# LED.net
KiCad netlist of a schematic drawn in Altium Designer
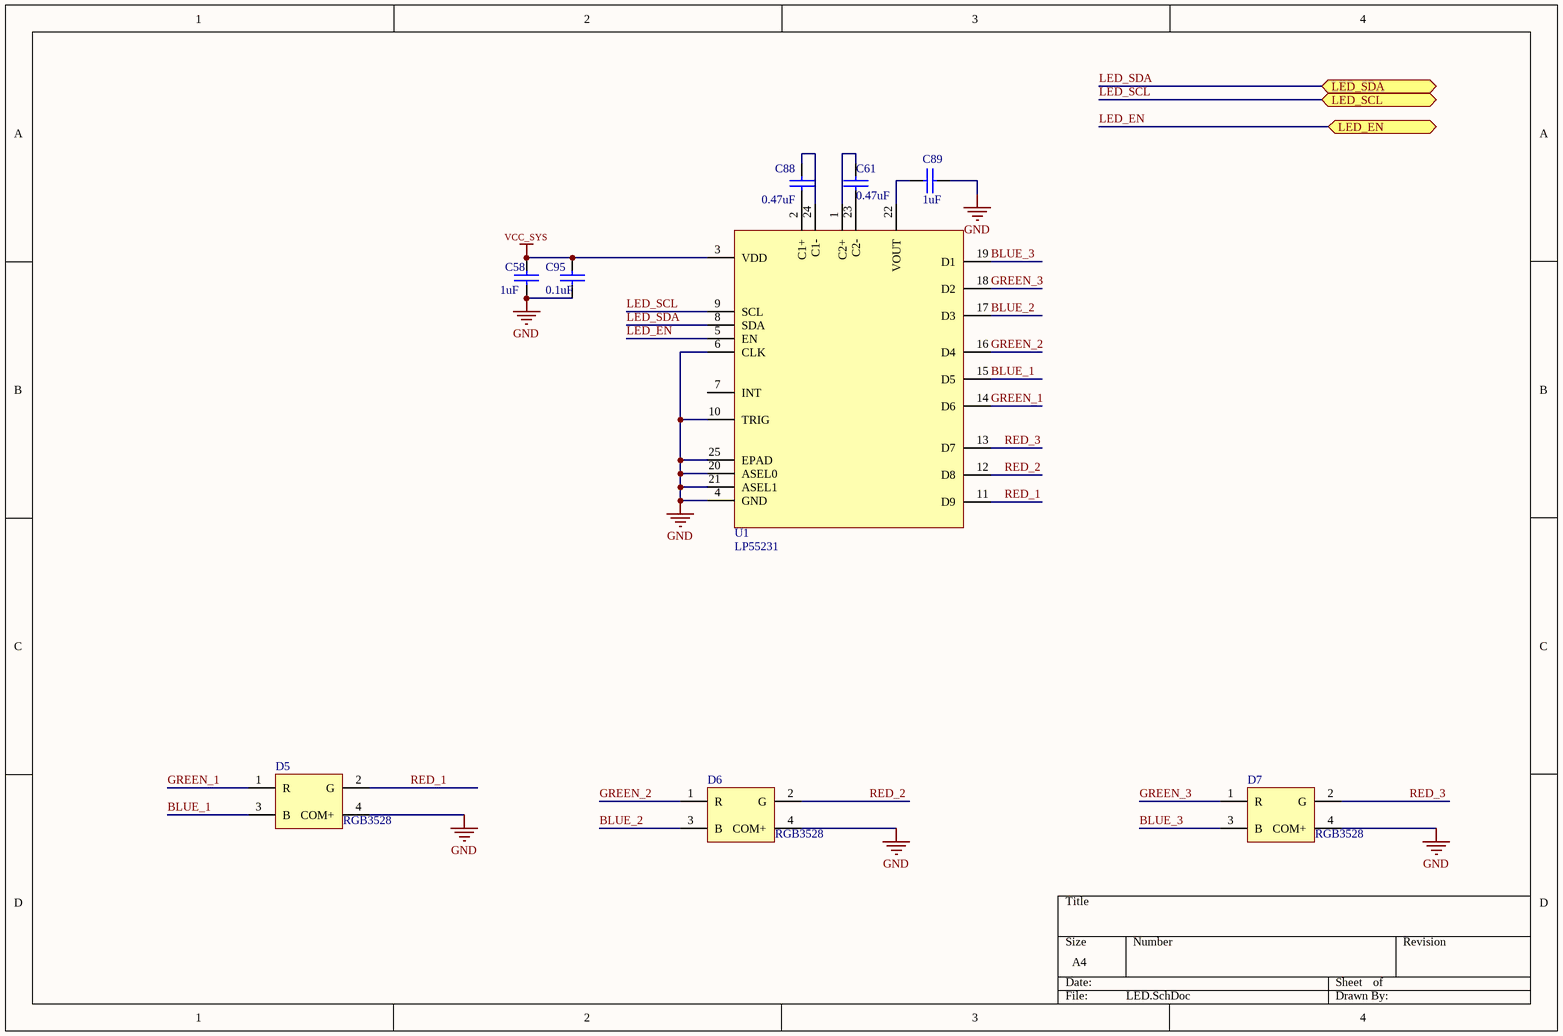
[diagram p0: LED.SchDoc]

(export (version "E")
  (design (tool "Eeschema 10.0.6"))
  (components
    (comp (ref "C58")
      (value "1uF")
      (footprint "0402C")
      (description "1uF/10V/X7R/10%，0402")
      (libsource (lib "Schlib1") (part "CAP"))
    )
    (comp (ref "C61")
      (value "0.47uF")
      (footprint "0402C")
      (description "0.1uF/10V/X7R/10%，0402")
      (libsource (lib "Schlib1") (part "CAP"))
    )
    (comp (ref "C88")
      (value "0.47uF")
      (footprint "0402C")
      (description "0.22uF/10V/X7R/10%，0402")
      (libsource (lib "Schlib1") (part "CAP"))
    )
    (comp (ref "C89")
      (value "1uF")
      (footprint "0402C")
      (description "0.22uF/10V/X7R/10%，0402")
      (libsource (lib "Schlib1") (part "CAP"))
    )
    (comp (ref "C95")
      (value "0.1uF")
      (footprint "0402C")
      (description "0.1uF/10V/X7R/10%，0402")
      (libsource (lib "Schlib1") (part "CAP"))
    )
    (comp (ref "D5")
      (value "RGB3528")
      (footprint "19-237B/R6GHBHC-C01/2T")
      (fields (field (name "PUBLISHER") "Altium Limited"))
      (libsource (lib "常用sch库") (part "RGB3528"))
    )
    (comp (ref "D6")
      (value "RGB3528")
      (footprint "19-237B/R6GHBHC-C01/2T")
      (fields (field (name "PUBLISHER") "Altium Limited"))
      (libsource (lib "常用sch库") (part "RGB3528"))
    )
    (comp (ref "D7")
      (value "RGB3528")
      (footprint "19-237B/R6GHBHC-C01/2T")
      (fields (field (name "PUBLISHER") "Altium Limited"))
      (libsource (lib "常用sch库") (part "RGB3528"))
    )
    (comp (ref "U1")
      (value "LP55231")
      (footprint "WQFN24")
      (description "厂家：SI-EN，型号：IS31FL3199-QFLS2-TR")
      (libsource (lib "button_1") (part "SN3199"))
    )
  )
  (nets
    (net (code "1") (name "/BLUE_1") (class "Default")
      (node (ref "D5") (pin "3") (pinfunction "B_3") (pintype "passive"))
      (node (ref "U1") (pin "15") (pinfunction "D5_15") (pintype "passive"))
    )
    (net (code "2") (name "/BLUE_2") (class "Default")
      (node (ref "D6") (pin "3") (pinfunction "B_3") (pintype "passive"))
      (node (ref "U1") (pin "17") (pinfunction "D3_17") (pintype "passive"))
    )
    (net (code "3") (name "/BLUE_3") (class "Default")
      (node (ref "D7") (pin "3") (pinfunction "B_3") (pintype "passive"))
      (node (ref "U1") (pin "19") (pinfunction "D1_19") (pintype "passive"))
    )
    (net (code "4") (name "/GREEN_1") (class "Default")
      (node (ref "D5") (pin "1") (pinfunction "R_1") (pintype "passive"))
      (node (ref "U1") (pin "14") (pinfunction "D6_14") (pintype "passive"))
    )
    (net (code "5") (name "/GREEN_2") (class "Default")
      (node (ref "D6") (pin "1") (pinfunction "R_1") (pintype "passive"))
      (node (ref "U1") (pin "16") (pinfunction "D4_16") (pintype "passive"))
    )
    (net (code "6") (name "/GREEN_3") (class "Default")
      (node (ref "D7") (pin "1") (pinfunction "R_1") (pintype "passive"))
      (node (ref "U1") (pin "18") (pinfunction "D2_18") (pintype "passive"))
    )
    (net (code "7") (name "/LED_EN") (class "Default")
      (node (ref "U1") (pin "5") (pinfunction "EN_5") (pintype "passive"))
    )
    (net (code "8") (name "/LED_SCL") (class "Default")
      (node (ref "U1") (pin "9") (pinfunction "SCL_9") (pintype "passive"))
    )
    (net (code "9") (name "/LED_SDA") (class "Default")
      (node (ref "U1") (pin "8") (pinfunction "SDA_8") (pintype "passive"))
    )
    (net (code "10") (name "/RED_1") (class "Default")
      (node (ref "D5") (pin "2") (pinfunction "G_2") (pintype "passive"))
      (node (ref "U1") (pin "11") (pinfunction "D9_11") (pintype "passive"))
    )
    (net (code "11") (name "/RED_2") (class "Default")
      (node (ref "D6") (pin "2") (pinfunction "G_2") (pintype "passive"))
      (node (ref "U1") (pin "12") (pinfunction "D8_12") (pintype "passive"))
    )
    (net (code "12") (name "/RED_3") (class "Default")
      (node (ref "D7") (pin "2") (pinfunction "G_2") (pintype "passive"))
      (node (ref "U1") (pin "13") (pinfunction "D7_13") (pintype "passive"))
    )
    (net (code "13") (name "GND") (class "Default")
      (node (ref "C58") (pin "2") (pinfunction "2_2") (pintype "passive"))
      (node (ref "C89") (pin "1") (pinfunction "1_1") (pintype "passive"))
      (node (ref "C95") (pin "2") (pinfunction "2_2") (pintype "passive"))
      (node (ref "D5") (pin "4") (pinfunction "COM+_4") (pintype "passive"))
      (node (ref "D6") (pin "4") (pinfunction "COM+_4") (pintype "passive"))
      (node (ref "D7") (pin "4") (pinfunction "COM+_4") (pintype "passive"))
      (node (ref "U1") (pin "10") (pinfunction "TRIG_10") (pintype "passive"))
      (node (ref "U1") (pin "20") (pinfunction "ASEL0_20") (pintype "passive"))
      (node (ref "U1") (pin "21") (pinfunction "ASEL1_21") (pintype "passive"))
      (node (ref "U1") (pin "25") (pinfunction "EPAD_25") (pintype "passive"))
      (node (ref "U1") (pin "4") (pinfunction "GND_4") (pintype "passive"))
      (node (ref "U1") (pin "6") (pinfunction "CLK_6") (pintype "passive"))
    )
    (net (code "14") (name "Net-(U1-C1+)") (class "Default")
      (node (ref "C88") (pin "1") (pinfunction "1_1") (pintype "passive"))
      (node (ref "U1") (pin "2") (pinfunction "C1+_2") (pintype "passive"))
    )
    (net (code "15") (name "Net-(U1-C1-)") (class "Default")
      (node (ref "C88") (pin "2") (pinfunction "2_2") (pintype "passive"))
      (node (ref "U1") (pin "24") (pinfunction "C1-_24") (pintype "passive"))
    )
    (net (code "16") (name "Net-(U1-C2+)") (class "Default")
      (node (ref "C61") (pin "1") (pinfunction "1_1") (pintype "passive"))
      (node (ref "U1") (pin "1") (pinfunction "C2+_1") (pintype "passive"))
    )
    (net (code "17") (name "Net-(U1-C2-)") (class "Default")
      (node (ref "C61") (pin "2") (pinfunction "2_2") (pintype "passive"))
      (node (ref "U1") (pin "23") (pinfunction "C2-_23") (pintype "passive"))
    )
    (net (code "18") (name "Net-(U1-VOUT)") (class "Default")
      (node (ref "C89") (pin "2") (pinfunction "2_2") (pintype "passive"))
      (node (ref "U1") (pin "22") (pinfunction "VOUT_22") (pintype "passive"))
    )
    (net (code "19") (name "VCC_SYS") (class "Default")
      (node (ref "C58") (pin "1") (pinfunction "1_1") (pintype "passive"))
      (node (ref "C95") (pin "1") (pinfunction "1_1") (pintype "passive"))
      (node (ref "U1") (pin "3") (pinfunction "VDD_3") (pintype "passive"))
    )
    (net (code "20") (name "unconnected-(U1-INT-Pad7)") (class "Default")
      (node (ref "U1") (pin "7") (pinfunction "INT_7") (pintype "passive"))
    )
  )
)
